# gator-bit.net
KiCad netlist of a schematic drawn in EAGLE
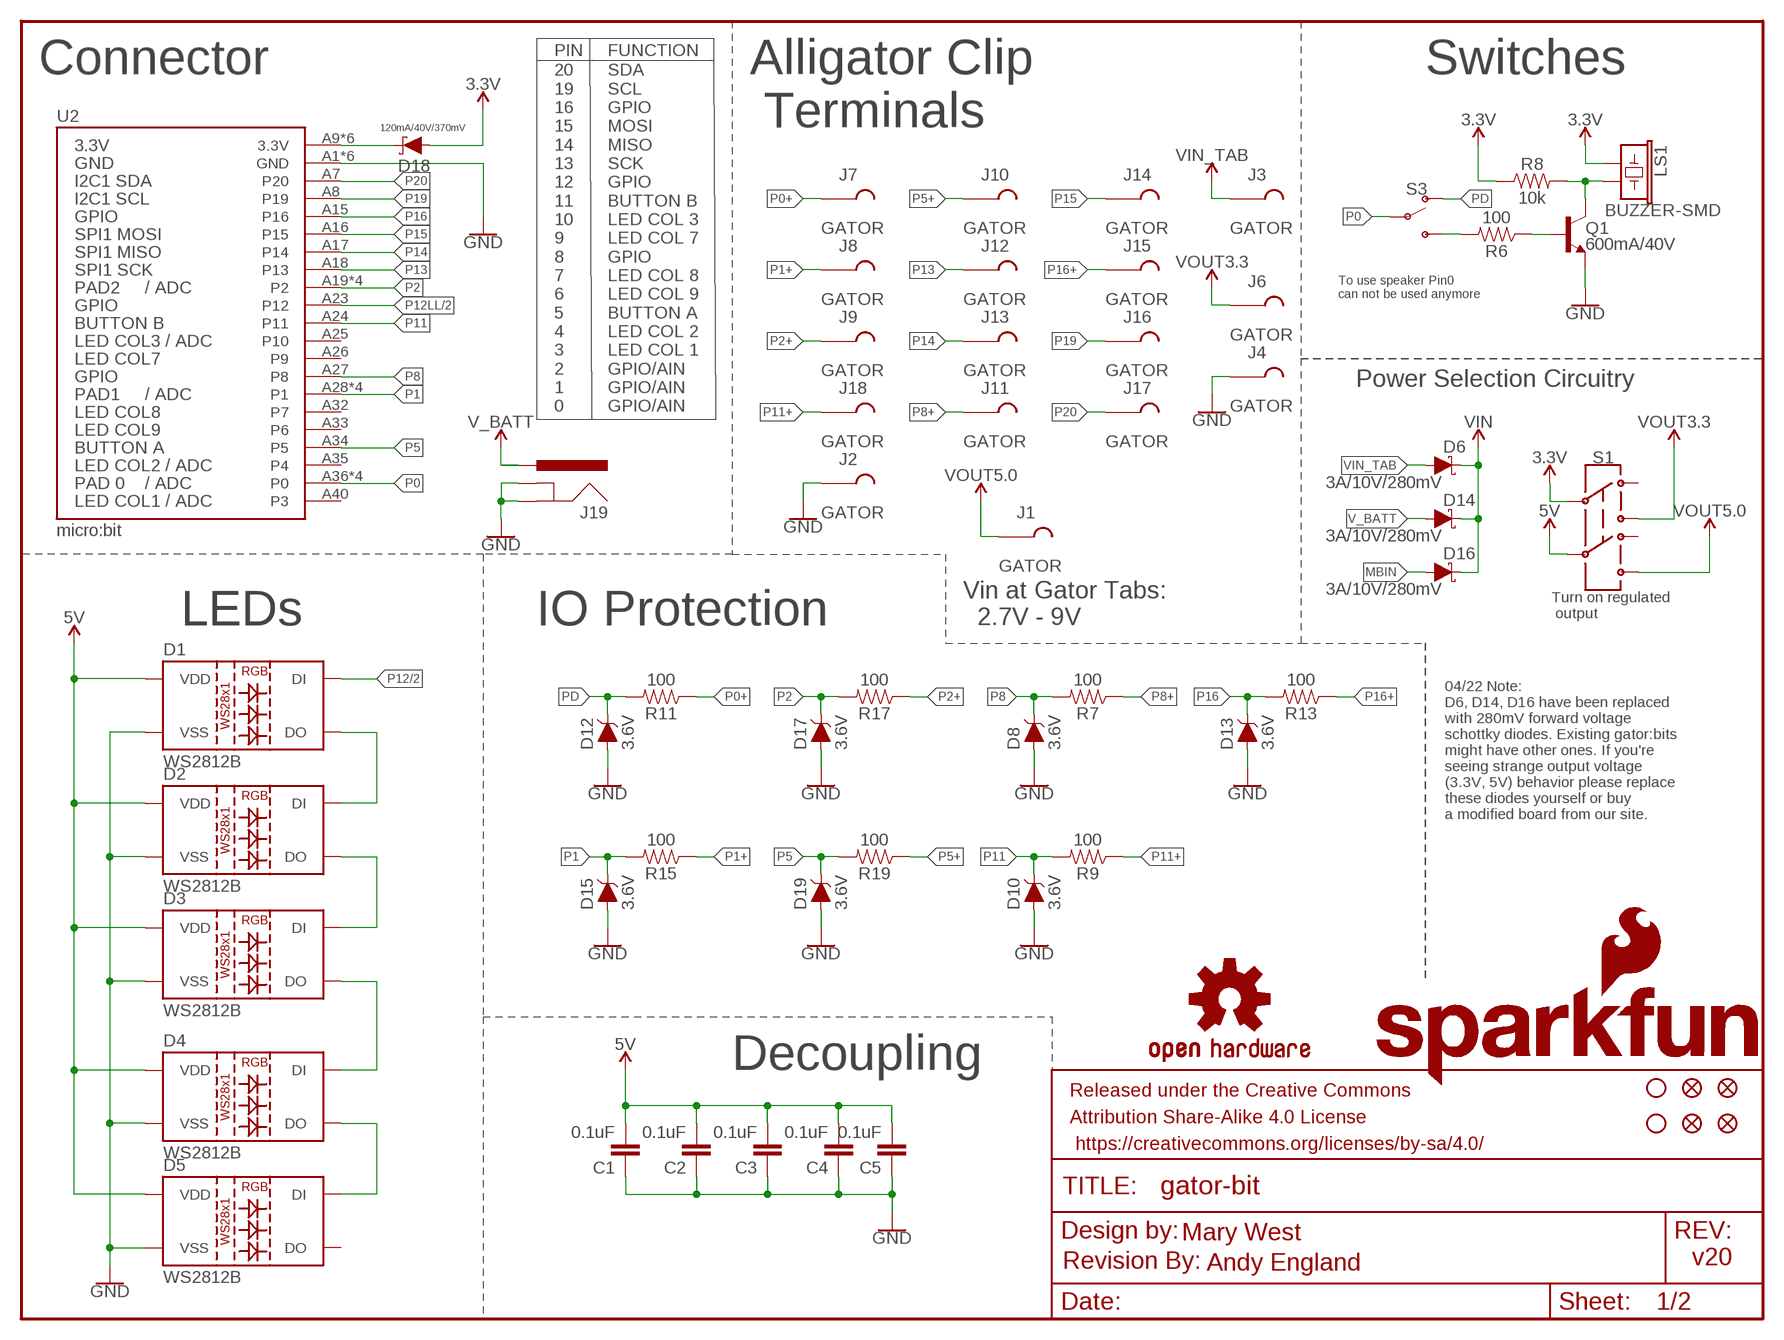
[diagram p0: schematic, sheet 1]
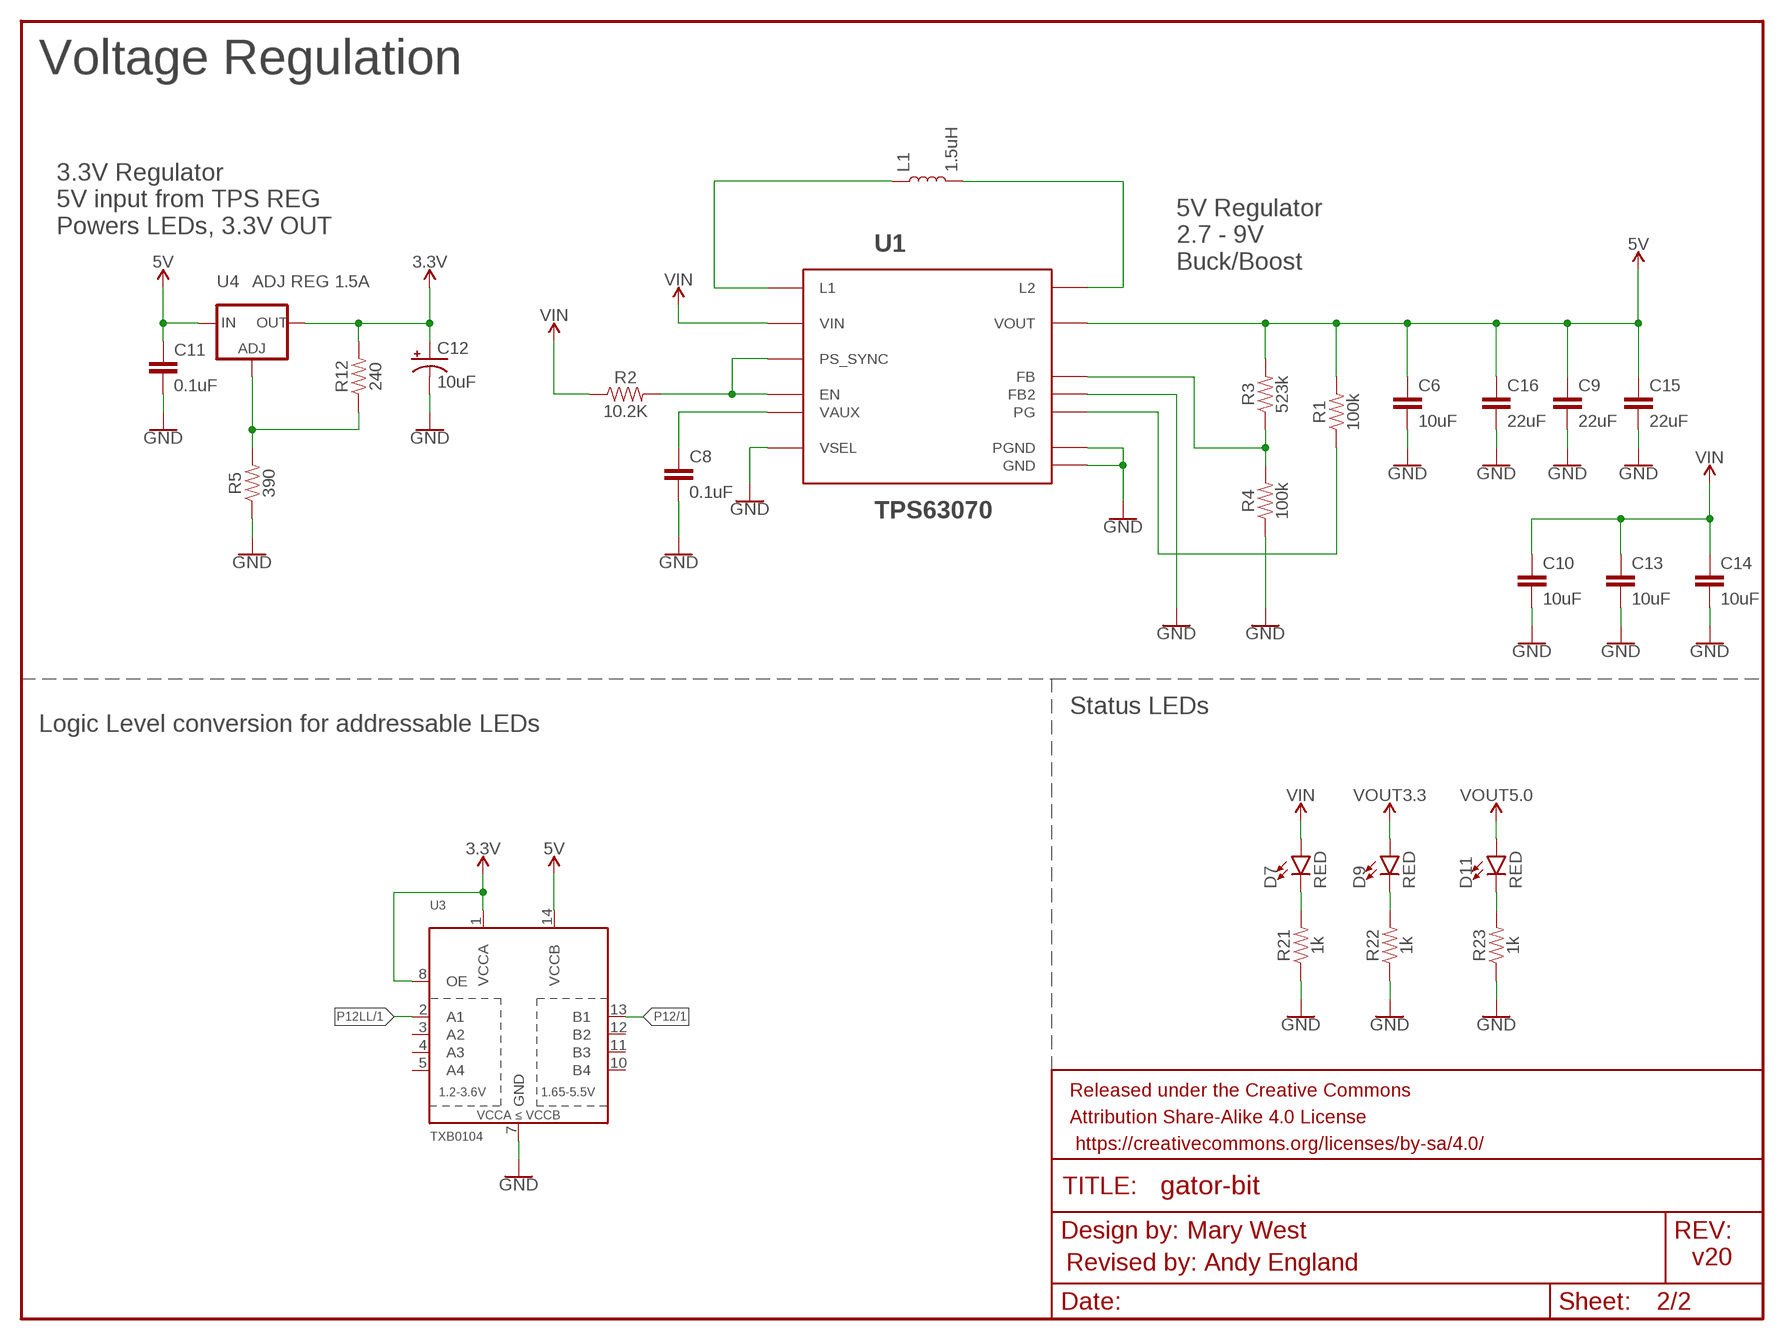
[diagram p1: schematic, sheet 2]

(export (version "E")
  (design (tool "Eeschema 10.0.6"))
  (components
    (comp (ref "C6")
      (value "10uF")
      (footprint "eagle-import:0603")
      (libsource (lib "eagle-import") (part "10UF-0603-6.3V-20%"))
    )
    (comp (ref "C8")
      (value "0.1uF")
      (footprint "eagle-import:0603")
      (libsource (lib "eagle-import") (part "0.1UF-0603-25V-(+80/-20%)"))
    )
    (comp (ref "C9")
      (value "22uF")
      (footprint "eagle-import:0805")
      (libsource (lib "eagle-import") (part "22UF-0805-6.3V-20%"))
    )
    (comp (ref "C10")
      (value "10uF")
      (footprint "eagle-import:0805")
      (libsource (lib "eagle-import") (part "10UF-0805-10V-10%"))
    )
    (comp (ref "C11")
      (value "0.1uF")
      (footprint "eagle-import:0603")
      (libsource (lib "eagle-import") (part "0.1UF-0603-25V-(+80/-20%)"))
    )
    (comp (ref "C12")
      (value "10uF")
      (footprint "eagle-import:EIA3216")
      (libsource (lib "eagle-import") (part "10UF-POLAR-EIA3216-16V-10%(TANT)"))
    )
    (comp (ref "C13")
      (value "10uF")
      (footprint "eagle-import:0805")
      (libsource (lib "eagle-import") (part "10UF-0805-10V-10%"))
    )
    (comp (ref "C14")
      (value "10uF")
      (footprint "eagle-import:0603")
      (libsource (lib "eagle-import") (part "10UF-0603-6.3V-20%"))
    )
    (comp (ref "C15")
      (value "22uF")
      (footprint "eagle-import:0805")
      (libsource (lib "eagle-import") (part "22UF-0805-6.3V-20%"))
    )
    (comp (ref "C16")
      (value "22uF")
      (footprint "eagle-import:0805")
      (libsource (lib "eagle-import") (part "22UF-0805-6.3V-20%"))
    )
    (comp (ref "D7")
      (value "RED")
      (footprint "eagle-import:LED-0603")
      (libsource (lib "eagle-import") (part "LED-RED0603"))
    )
    (comp (ref "D9")
      (value "RED")
      (footprint "eagle-import:LED-0603")
      (libsource (lib "eagle-import") (part "LED-RED0603"))
    )
    (comp (ref "D11")
      (value "RED")
      (footprint "eagle-import:LED-0603")
      (libsource (lib "eagle-import") (part "LED-RED0603"))
    )
    (comp (ref "FRAME3")
      (value "FRAME-LETTER")
      (footprint "eagle-import:CREATIVE_COMMONS")
      (libsource (lib "eagle-import") (part "FRAME-LETTER"))
    )
    (comp (ref "L1")
      (value "1.5uH")
      (footprint "eagle-import:XFL4020")
      (libsource (lib "eagle-import") (part "INDUCTOR-XFL40201.5UH"))
    )
    (comp (ref "R1")
      (value "100k")
      (footprint "eagle-import:0603")
      (libsource (lib "eagle-import") (part "100KOHM-0603-1/10W-1%"))
    )
    (comp (ref "R2")
      (value "10.2K")
      (footprint "eagle-import:0603")
      (libsource (lib "eagle-import") (part "10.2KOHM"))
    )
    (comp (ref "R3")
      (value "523k")
      (footprint "eagle-import:0603")
      (libsource (lib "eagle-import") (part "523KOHMOHMS-0603-1/10W-1%"))
    )
    (comp (ref "R4")
      (value "100k")
      (footprint "eagle-import:0603")
      (libsource (lib "eagle-import") (part "100KOHM-0603-1/10W-1%"))
    )
    (comp (ref "R5")
      (value "390")
      (footprint "eagle-import:0603")
      (libsource (lib "eagle-import") (part "390OHM-0603-1/10W-1%"))
    )
    (comp (ref "R12")
      (value "240")
      (footprint "eagle-import:0603")
      (libsource (lib "eagle-import") (part "240OHM-0603-1/10W-1%"))
    )
    (comp (ref "R21")
      (value "1k")
      (footprint "eagle-import:0603")
      (libsource (lib "eagle-import") (part "1KOHM-0603-1/10W-1%"))
    )
    (comp (ref "R22")
      (value "1k")
      (footprint "eagle-import:0603")
      (libsource (lib "eagle-import") (part "1KOHM-0603-1/10W-1%"))
    )
    (comp (ref "R23")
      (value "1k")
      (footprint "eagle-import:0603")
      (libsource (lib "eagle-import") (part "1KOHM-0603-1/10W-1%"))
    )
    (comp (ref "U1")
      (value "TPS63070")
      (footprint "eagle-import:TPS63070RNM")
      (libsource (lib "eagle-import") (part "TPS63070RNM"))
    )
    (comp (ref "U3")
      (value "TXB0104")
      (footprint "eagle-import:TSSOP14")
      (libsource (lib "eagle-import") (part "TXB0104PWR"))
    )
    (comp (ref "U4")
      (value "ADJ REG 1.5A")
      (footprint "eagle-import:SOT223")
      (libsource (lib "eagle-import") (part "GATORBIT_LM317"))
    )
    (comp (ref "C1")
      (value "0.1uF")
      (footprint "eagle-import:0603")
      (libsource (lib "eagle-import") (part "0.1UF-0603-25V-(+80/-20%)"))
    )
    (comp (ref "C2")
      (value "0.1uF")
      (footprint "eagle-import:0603")
      (libsource (lib "eagle-import") (part "0.1UF-0603-25V-(+80/-20%)"))
    )
    (comp (ref "C3")
      (value "0.1uF")
      (footprint "eagle-import:0603")
      (libsource (lib "eagle-import") (part "0.1UF-0603-25V-(+80/-20%)"))
    )
    (comp (ref "C4")
      (value "0.1uF")
      (footprint "eagle-import:0603")
      (libsource (lib "eagle-import") (part "0.1UF-0603-25V-(+80/-20%)"))
    )
    (comp (ref "C5")
      (value "0.1uF")
      (footprint "eagle-import:0603")
      (libsource (lib "eagle-import") (part "0.1UF-0603-25V-(+80/-20%)"))
    )
    (comp (ref "D1")
      (value "WS2812B")
      (footprint "eagle-import:WS2812B")
      (libsource (lib "eagle-import") (part "WS2812B"))
    )
    (comp (ref "D2")
      (value "WS2812B")
      (footprint "eagle-import:WS2812B")
      (libsource (lib "eagle-import") (part "WS2812B"))
    )
    (comp (ref "D3")
      (value "WS2812B")
      (footprint "eagle-import:WS2812B")
      (libsource (lib "eagle-import") (part "WS2812B"))
    )
    (comp (ref "D4")
      (value "WS2812B")
      (footprint "eagle-import:WS2812B")
      (libsource (lib "eagle-import") (part "WS2812B"))
    )
    (comp (ref "D5")
      (value "WS2812B")
      (footprint "eagle-import:WS2812B")
      (libsource (lib "eagle-import") (part "WS2812B"))
    )
    (comp (ref "D6")
      (value "3A/10V/280mV")
      (footprint "eagle-import:SOD-323")
      (libsource (lib "eagle-import") (part "DIODE-SCHOTTKY-BAT60A"))
    )
    (comp (ref "D8")
      (value "3.6V")
      (footprint "eagle-import:SOD-323")
      (libsource (lib "eagle-import") (part "DIODE-ZENER-BZT52C3V6S"))
    )
    (comp (ref "D10")
      (value "3.6V")
      (footprint "eagle-import:SOD-323")
      (libsource (lib "eagle-import") (part "DIODE-ZENER-BZT52C3V6S"))
    )
    (comp (ref "D12")
      (value "3.6V")
      (footprint "eagle-import:SOD-323")
      (libsource (lib "eagle-import") (part "DIODE-ZENER-BZT52C3V6S"))
    )
    (comp (ref "D13")
      (value "3.6V")
      (footprint "eagle-import:SOD-323")
      (libsource (lib "eagle-import") (part "DIODE-ZENER-BZT52C3V6S"))
    )
    (comp (ref "D14")
      (value "3A/10V/280mV")
      (footprint "eagle-import:SOD-323")
      (libsource (lib "eagle-import") (part "DIODE-SCHOTTKY-BAT60A"))
    )
    (comp (ref "D15")
      (value "3.6V")
      (footprint "eagle-import:SOD-323")
      (libsource (lib "eagle-import") (part "DIODE-ZENER-BZT52C3V6S"))
    )
    (comp (ref "D16")
      (value "3A/10V/280mV")
      (footprint "eagle-import:SOD-323")
      (libsource (lib "eagle-import") (part "DIODE-SCHOTTKY-BAT60A"))
    )
    (comp (ref "D17")
      (value "3.6V")
      (footprint "eagle-import:SOD-323")
      (libsource (lib "eagle-import") (part "DIODE-ZENER-BZT52C3V6S"))
    )
    (comp (ref "D18")
      (value "120mA/40V/370mV")
      (footprint "eagle-import:SOD-523")
      (libsource (lib "eagle-import") (part "DIODE-SCHOTTKY-RB751S40"))
    )
    (comp (ref "D19")
      (value "3.6V")
      (footprint "eagle-import:SOD-323")
      (libsource (lib "eagle-import") (part "DIODE-ZENER-BZT52C3V6S"))
    )
    (comp (ref "FD1")
      (value "FIDUCIAL1X2")
      (footprint "eagle-import:FIDUCIAL-1X2")
      (libsource (lib "eagle-import") (part "FIDUCIAL1X2"))
    )
    (comp (ref "FD2")
      (value "FIDUCIAL1X2")
      (footprint "eagle-import:FIDUCIAL-1X2")
      (libsource (lib "eagle-import") (part "FIDUCIAL1X2"))
    )
    (comp (ref "FD3")
      (value "FIDUCIAL1X2")
      (footprint "eagle-import:FIDUCIAL-1X2")
      (libsource (lib "eagle-import") (part "FIDUCIAL1X2"))
    )
    (comp (ref "FD4")
      (value "FIDUCIAL1X2")
      (footprint "eagle-import:FIDUCIAL-1X2")
      (libsource (lib "eagle-import") (part "FIDUCIAL1X2"))
    )
    (comp (ref "FRAME1")
      (value "FRAME-LETTER")
      (footprint "eagle-import:CREATIVE_COMMONS")
      (libsource (lib "eagle-import") (part "FRAME-LETTER"))
    )
    (comp (ref "H1")
      (value "STAND-OFF")
      (footprint "eagle-import:STAND-OFF")
      (libsource (lib "eagle-import") (part "STAND-OFF"))
    )
    (comp (ref "H2")
      (value "STAND-OFF")
      (footprint "eagle-import:STAND-OFF")
      (libsource (lib "eagle-import") (part "STAND-OFF"))
    )
    (comp (ref "J1")
      (value "GATOR")
      (footprint "eagle-import:GATOR")
      (libsource (lib "eagle-import") (part "GATOR"))
    )
    (comp (ref "J2")
      (value "GATOR")
      (footprint "eagle-import:GATOR")
      (libsource (lib "eagle-import") (part "GATOR"))
    )
    (comp (ref "J3")
      (value "GATOR")
      (footprint "eagle-import:GATOR")
      (libsource (lib "eagle-import") (part "GATOR"))
    )
    (comp (ref "J4")
      (value "GATOR")
      (footprint "eagle-import:GATOR")
      (libsource (lib "eagle-import") (part "GATOR"))
    )
    (comp (ref "J6")
      (value "GATOR")
      (footprint "eagle-import:GATOR")
      (libsource (lib "eagle-import") (part "GATOR"))
    )
    (comp (ref "J7")
      (value "GATOR")
      (footprint "eagle-import:GATOR")
      (libsource (lib "eagle-import") (part "GATOR"))
    )
    (comp (ref "J8")
      (value "GATOR")
      (footprint "eagle-import:GATOR")
      (libsource (lib "eagle-import") (part "GATOR"))
    )
    (comp (ref "J9")
      (value "GATOR")
      (footprint "eagle-import:GATOR")
      (libsource (lib "eagle-import") (part "GATOR"))
    )
    (comp (ref "J10")
      (value "GATOR")
      (footprint "eagle-import:GATOR")
      (libsource (lib "eagle-import") (part "GATOR"))
    )
    (comp (ref "J11")
      (value "GATOR")
      (footprint "eagle-import:GATOR")
      (libsource (lib "eagle-import") (part "GATOR"))
    )
    (comp (ref "J12")
      (value "GATOR")
      (footprint "eagle-import:GATOR")
      (libsource (lib "eagle-import") (part "GATOR"))
    )
    (comp (ref "J13")
      (value "GATOR")
      (footprint "eagle-import:GATOR")
      (libsource (lib "eagle-import") (part "GATOR"))
    )
    (comp (ref "J14")
      (value "GATOR")
      (footprint "eagle-import:GATOR")
      (libsource (lib "eagle-import") (part "GATOR"))
    )
    (comp (ref "J15")
      (value "GATOR")
      (footprint "eagle-import:GATOR")
      (libsource (lib "eagle-import") (part "GATOR"))
    )
    (comp (ref "J16")
      (value "GATOR")
      (footprint "eagle-import:GATOR")
      (libsource (lib "eagle-import") (part "GATOR"))
    )
    (comp (ref "J17")
      (value "GATOR")
      (footprint "eagle-import:GATOR")
      (libsource (lib "eagle-import") (part "GATOR"))
    )
    (comp (ref "J18")
      (value "GATOR")
      (footprint "eagle-import:GATOR")
      (libsource (lib "eagle-import") (part "GATOR"))
    )
    (comp (ref "J19")
      (value "POWER_JACKPTH_LOCK")
      (footprint "eagle-import:POWER_JACK_PTH_LOCK")
      (libsource (lib "eagle-import") (part "POWER_JACKPTH_LOCK"))
    )
    (comp (ref "LOGO1")
      (value "SFE_LOGO_NAME_FLAME.3_INCH")
      (footprint "eagle-import:SFE_LOGO_NAME_FLAME_.3")
      (libsource (lib "eagle-import") (part "SFE_LOGO_NAME_FLAME.3_INCH"))
    )
    (comp (ref "LOGO2")
      (value "OSHW-LOGOM")
      (footprint "eagle-import:OSHW-LOGO-M")
      (libsource (lib "eagle-import") (part "OSHW-LOGOM"))
    )
    (comp (ref "LOGO3")
      (value "REVISION")
      (footprint "eagle-import:REVISION")
      (libsource (lib "eagle-import") (part "REVISION"))
    )
    (comp (ref "LS1")
      (value "BUZZER-SMD")
      (footprint "eagle-import:BUZZER-CCV")
      (libsource (lib "eagle-import") (part "BUZZER-SMD"))
    )
    (comp (ref "Q1")
      (value "600mA/40V")
      (footprint "eagle-import:SOT23-3")
      (libsource (lib "eagle-import") (part "TRANS_NPN-MMBT2222AL"))
    )
    (comp (ref "R6")
      (value "100")
      (footprint "eagle-import:0603")
      (libsource (lib "eagle-import") (part "100OHM-0603-1/10W-1%"))
    )
    (comp (ref "R7")
      (value "100")
      (footprint "eagle-import:0603")
      (libsource (lib "eagle-import") (part "100OHM-0603-1/10W-1%"))
    )
    (comp (ref "R8")
      (value "10k")
      (footprint "eagle-import:0603")
      (libsource (lib "eagle-import") (part "10KOHM-0603-1/10W-1%"))
    )
    (comp (ref "R9")
      (value "100")
      (footprint "eagle-import:0603")
      (libsource (lib "eagle-import") (part "100OHM-0603-1/10W-1%"))
    )
    (comp (ref "R11")
      (value "100")
      (footprint "eagle-import:0603")
      (libsource (lib "eagle-import") (part "100OHM-0603-1/10W-1%"))
    )
    (comp (ref "R13")
      (value "100")
      (footprint "eagle-import:0603")
      (libsource (lib "eagle-import") (part "100OHM-0603-1/10W-1%"))
    )
    (comp (ref "R15")
      (value "100")
      (footprint "eagle-import:0603")
      (libsource (lib "eagle-import") (part "100OHM-0603-1/10W-1%"))
    )
    (comp (ref "R17")
      (value "100")
      (footprint "eagle-import:0603")
      (libsource (lib "eagle-import") (part "100OHM-0603-1/10W-1%"))
    )
    (comp (ref "R19")
      (value "100")
      (footprint "eagle-import:0603")
      (libsource (lib "eagle-import") (part "100OHM-0603-1/10W-1%"))
    )
    (comp (ref "S1")
      (value "SWITCH-DPDT-SMD-AYZ0202")
      (footprint "eagle-import:SWITCH_DPDT_SMD_AYZ0202")
      (libsource (lib "eagle-import") (part "SWITCH-DPDT-SMD-AYZ0202"))
    )
    (comp (ref "S3")
      (value "SWITCH-SPDT-SMD-AYZ0202")
      (footprint "eagle-import:SWITCH_DPDT_SMD_AYZ0202")
      (libsource (lib "eagle-import") (part "SWITCH-SPDT-SMD-AYZ0202"))
    )
    (comp (ref "U2")
      (value "micro:bit")
      (footprint "eagle-import:MICRO_BIT_RA_PTH")
      (libsource (lib "eagle-import") (part "MICRO{colon}BITLEDS_UP"))
    )
  )
  (nets
    (net (code "1") (name "3.3V") (class "Default")
      (node (ref "C12") (pin "+") (pinfunction "+_+") (pintype "passive"))
      (node (ref "D18") (pin "A") (pinfunction "A_A") (pintype "passive"))
      (node (ref "LS1") (pin "+") (pinfunction "1_+") (pintype "passive"))
      (node (ref "R12") (pin "2") (pinfunction "2_2") (pintype "passive"))
      (node (ref "R8") (pin "1") (pinfunction "1_1") (pintype "passive"))
      (node (ref "S1") (pin "2") (pinfunction "2_2") (pintype "bidirectional"))
      (node (ref "U3") (pin "1") (pinfunction "VCCA_1") (pintype "bidirectional"))
      (node (ref "U3") (pin "8") (pinfunction "OE_8") (pintype "bidirectional"))
      (node (ref "U4") (pin "2") (pinfunction "OUT_2") (pintype "output"))
      (node (ref "U4") (pin "4") (pinfunction "OUT_4") (pintype "output"))
    )
    (net (code "2") (name "5V") (class "Default")
      (node (ref "C1") (pin "2") (pinfunction "2_2") (pintype "passive"))
      (node (ref "C11") (pin "1") (pinfunction "1_1") (pintype "passive"))
      (node (ref "C15") (pin "1") (pinfunction "1_1") (pintype "passive"))
      (node (ref "C16") (pin "1") (pinfunction "1_1") (pintype "passive"))
      (node (ref "C2") (pin "2") (pinfunction "2_2") (pintype "passive"))
      (node (ref "C3") (pin "2") (pinfunction "2_2") (pintype "passive"))
      (node (ref "C4") (pin "2") (pinfunction "2_2") (pintype "passive"))
      (node (ref "C5") (pin "2") (pinfunction "2_2") (pintype "passive"))
      (node (ref "C6") (pin "1") (pinfunction "1_1") (pintype "passive"))
      (node (ref "C9") (pin "1") (pinfunction "1_1") (pintype "passive"))
      (node (ref "D1") (pin "1") (pinfunction "VDD_1") (pintype "bidirectional"))
      (node (ref "D2") (pin "1") (pinfunction "VDD_1") (pintype "bidirectional"))
      (node (ref "D3") (pin "1") (pinfunction "VDD_1") (pintype "bidirectional"))
      (node (ref "D4") (pin "1") (pinfunction "VDD_1") (pintype "bidirectional"))
      (node (ref "D5") (pin "1") (pinfunction "VDD_1") (pintype "bidirectional"))
      (node (ref "R1") (pin "2") (pinfunction "2_2") (pintype "passive"))
      (node (ref "R3") (pin "2") (pinfunction "2_2") (pintype "passive"))
      (node (ref "S1") (pin "5") (pinfunction "5_5") (pintype "bidirectional"))
      (node (ref "U1") (pin "P$7") (pinfunction "VOUT_P$7") (pintype "bidirectional"))
      (node (ref "U3") (pin "14") (pinfunction "VCCB_14") (pintype "bidirectional"))
      (node (ref "U4") (pin "3") (pinfunction "IN_3") (pintype "input"))
    )
    (net (code "3") (name "GND") (class "Default")
      (node (ref "C1") (pin "1") (pinfunction "1_1") (pintype "passive"))
      (node (ref "C10") (pin "2") (pinfunction "2_2") (pintype "passive"))
      (node (ref "C11") (pin "2") (pinfunction "2_2") (pintype "passive"))
      (node (ref "C12") (pin "-") (pinfunction "-_-") (pintype "passive"))
      (node (ref "C13") (pin "2") (pinfunction "2_2") (pintype "passive"))
      (node (ref "C14") (pin "2") (pinfunction "2_2") (pintype "passive"))
      (node (ref "C15") (pin "2") (pinfunction "2_2") (pintype "passive"))
      (node (ref "C16") (pin "2") (pinfunction "2_2") (pintype "passive"))
      (node (ref "C2") (pin "1") (pinfunction "1_1") (pintype "passive"))
      (node (ref "C3") (pin "1") (pinfunction "1_1") (pintype "passive"))
      (node (ref "C4") (pin "1") (pinfunction "1_1") (pintype "passive"))
      (node (ref "C5") (pin "1") (pinfunction "1_1") (pintype "passive"))
      (node (ref "C6") (pin "2") (pinfunction "2_2") (pintype "passive"))
      (node (ref "C8") (pin "2") (pinfunction "2_2") (pintype "passive"))
      (node (ref "C9") (pin "2") (pinfunction "2_2") (pintype "passive"))
      (node (ref "D1") (pin "3") (pinfunction "VSS_3") (pintype "bidirectional"))
      (node (ref "D10") (pin "A") (pinfunction "A_A") (pintype "passive"))
      (node (ref "D12") (pin "A") (pinfunction "A_A") (pintype "passive"))
      (node (ref "D13") (pin "A") (pinfunction "A_A") (pintype "passive"))
      (node (ref "D15") (pin "A") (pinfunction "A_A") (pintype "passive"))
      (node (ref "D17") (pin "A") (pinfunction "A_A") (pintype "passive"))
      (node (ref "D19") (pin "A") (pinfunction "A_A") (pintype "passive"))
      (node (ref "D2") (pin "3") (pinfunction "VSS_3") (pintype "bidirectional"))
      (node (ref "D3") (pin "3") (pinfunction "VSS_3") (pintype "bidirectional"))
      (node (ref "D4") (pin "3") (pinfunction "VSS_3") (pintype "bidirectional"))
      (node (ref "D5") (pin "3") (pinfunction "VSS_3") (pintype "bidirectional"))
      (node (ref "D8") (pin "A") (pinfunction "A_A") (pintype "passive"))
      (node (ref "J19") (pin "GND") (pinfunction "GND_GND") (pintype "bidirectional"))
      (node (ref "J19") (pin "GNDBREAK") (pinfunction "GNDBREAK_GNDBREAK") (pintype "bidirectional"))
      (node (ref "J2") (pin "P$1") (pinfunction "P$1_P$1") (pintype "bidirectional"))
      (node (ref "J2") (pin "P$2") (pinfunction "P$1_P$2") (pintype "bidirectional"))
      (node (ref "J4") (pin "P$1") (pinfunction "P$1_P$1") (pintype "bidirectional"))
      (node (ref "J4") (pin "P$2") (pinfunction "P$1_P$2") (pintype "bidirectional"))
      (node (ref "Q1") (pin "2") (pinfunction "E_2") (pintype "passive"))
      (node (ref "R21") (pin "1") (pinfunction "1_1") (pintype "passive"))
      (node (ref "R22") (pin "1") (pinfunction "1_1") (pintype "passive"))
      (node (ref "R23") (pin "1") (pinfunction "1_1") (pintype "passive"))
      (node (ref "R4") (pin "1") (pinfunction "1_1") (pintype "passive"))
      (node (ref "R5") (pin "1") (pinfunction "1_1") (pintype "passive"))
      (node (ref "U1") (pin "P$10") (pinfunction "PGND_P$10") (pintype "bidirectional"))
      (node (ref "U1") (pin "P$15") (pinfunction "VSEL_P$15") (pintype "bidirectional"))
      (node (ref "U1") (pin "P$4") (pinfunction "GND_P$4") (pintype "bidirectional"))
      (node (ref "U1") (pin "P$6") (pinfunction "FB2_P$6") (pintype "bidirectional"))
      (node (ref "U2") (pin "A1") (pinfunction "GND_A1") (pintype "bidirectional"))
      (node (ref "U2") (pin "A2") (pinfunction "GND_A2") (pintype "bidirectional"))
      (node (ref "U2") (pin "A3") (pinfunction "GND_A3") (pintype "bidirectional"))
      (node (ref "U2") (pin "A4") (pinfunction "GND_A4") (pintype "bidirectional"))
      (node (ref "U2") (pin "A5") (pinfunction "GND_A5") (pintype "bidirectional"))
      (node (ref "U2") (pin "A6") (pinfunction "GND_A6") (pintype "bidirectional"))
      (node (ref "U3") (pin "7") (pinfunction "GND_7") (pintype "bidirectional"))
    )
    (net (code "4") (name "MBIN") (class "Default")
      (node (ref "D16") (pin "A") (pinfunction "A_A") (pintype "passive"))
      (node (ref "D18") (pin "C") (pinfunction "C_C") (pintype "passive"))
      (node (ref "U2") (pin "A10") (pinfunction "3.3V_A10") (pintype "bidirectional"))
      (node (ref "U2") (pin "A11") (pinfunction "3.3V_A11") (pintype "bidirectional"))
      (node (ref "U2") (pin "A12") (pinfunction "3.3V_A12") (pintype "bidirectional"))
      (node (ref "U2") (pin "A13") (pinfunction "3.3V_A13") (pintype "bidirectional"))
      (node (ref "U2") (pin "A14") (pinfunction "3.3V_A14") (pintype "bidirectional"))
      (node (ref "U2") (pin "A9") (pinfunction "3.3V_A9") (pintype "bidirectional"))
    )
    (net (code "5") (name "Net-(D1-DO)") (class "Default")
      (node (ref "D1") (pin "2") (pinfunction "DO_2") (pintype "bidirectional"))
      (node (ref "D2") (pin "4") (pinfunction "DI_4") (pintype "bidirectional"))
    )
    (net (code "6") (name "Net-(D2-DO)") (class "Default")
      (node (ref "D2") (pin "2") (pinfunction "DO_2") (pintype "bidirectional"))
      (node (ref "D3") (pin "4") (pinfunction "DI_4") (pintype "bidirectional"))
    )
    (net (code "7") (name "Net-(D3-DO)") (class "Default")
      (node (ref "D3") (pin "2") (pinfunction "DO_2") (pintype "bidirectional"))
      (node (ref "D4") (pin "4") (pinfunction "DI_4") (pintype "bidirectional"))
    )
    (net (code "8") (name "Net-(D4-DO)") (class "Default")
      (node (ref "D4") (pin "2") (pinfunction "DO_2") (pintype "bidirectional"))
      (node (ref "D5") (pin "4") (pinfunction "DI_4") (pintype "bidirectional"))
    )
    (net (code "9") (name "Net-(D7-PadC)") (class "Default")
      (node (ref "D7") (pin "C") (pinfunction "C_C") (pintype "passive"))
      (node (ref "R21") (pin "2") (pinfunction "2_2") (pintype "passive"))
    )
    (net (code "10") (name "Net-(D9-PadC)") (class "Default")
      (node (ref "D9") (pin "C") (pinfunction "C_C") (pintype "passive"))
      (node (ref "R22") (pin "2") (pinfunction "2_2") (pintype "passive"))
    )
    (net (code "11") (name "Net-(D11-PadC)") (class "Default")
      (node (ref "D11") (pin "C") (pinfunction "C_C") (pintype "passive"))
      (node (ref "R23") (pin "2") (pinfunction "2_2") (pintype "passive"))
    )
    (net (code "12") (name "Net-(L1-1)") (class "Default")
      (node (ref "L1") (pin "P$1") (pinfunction "1_P$1") (pintype "passive"))
      (node (ref "U1") (pin "P$11") (pinfunction "L1_P$11") (pintype "bidirectional"))
    )
    (net (code "13") (name "Net-(L1-2)") (class "Default")
      (node (ref "L1") (pin "P$2") (pinfunction "2_P$2") (pintype "passive"))
      (node (ref "U1") (pin "P$9") (pinfunction "L2_P$9") (pintype "bidirectional"))
    )
    (net (code "14") (name "Net-(LS1-2)") (class "Default")
      (node (ref "LS1") (pin "-") (pinfunction "2_-") (pintype "passive"))
      (node (ref "Q1") (pin "3") (pinfunction "C_3") (pintype "passive"))
      (node (ref "R8") (pin "2") (pinfunction "2_2") (pintype "passive"))
    )
    (net (code "15") (name "Net-(Q1-B)") (class "Default")
      (node (ref "Q1") (pin "1") (pinfunction "B_1") (pintype "passive"))
      (node (ref "R6") (pin "1") (pinfunction "1_1") (pintype "passive"))
    )
    (net (code "16") (name "Net-(S3-S)") (class "Default")
      (node (ref "R6") (pin "2") (pinfunction "2_2") (pintype "passive"))
      (node (ref "S3") (pin "3") (pinfunction "S_3") (pintype "passive"))
    )
    (net (code "17") (name "Net-(U1-EN)") (class "Default")
      (node (ref "R2") (pin "2") (pinfunction "2_2") (pintype "passive"))
      (node (ref "U1") (pin "P$1") (pinfunction "PS_SYNC_P$1") (pintype "bidirectional"))
      (node (ref "U1") (pin "P$14") (pinfunction "EN_P$14") (pintype "bidirectional"))
    )
    (net (code "18") (name "Net-(U1-FB)") (class "Default")
      (node (ref "R3") (pin "1") (pinfunction "1_1") (pintype "passive"))
      (node (ref "R4") (pin "2") (pinfunction "2_2") (pintype "passive"))
      (node (ref "U1") (pin "P$5") (pinfunction "FB_P$5") (pintype "bidirectional"))
    )
    (net (code "19") (name "Net-(U1-PG)") (class "Default")
      (node (ref "R1") (pin "1") (pinfunction "1_1") (pintype "passive"))
      (node (ref "U1") (pin "P$2") (pinfunction "PG_P$2") (pintype "bidirectional"))
    )
    (net (code "20") (name "Net-(U1-VAUX)") (class "Default")
      (node (ref "C8") (pin "1") (pinfunction "1_1") (pintype "passive"))
      (node (ref "U1") (pin "P$3") (pinfunction "VAUX_P$3") (pintype "bidirectional"))
    )
    (net (code "21") (name "Net-(U4-ADJ)") (class "Default")
      (node (ref "R12") (pin "1") (pinfunction "1_1") (pintype "passive"))
      (node (ref "R5") (pin "2") (pinfunction "2_2") (pintype "passive"))
      (node (ref "U4") (pin "1") (pinfunction "ADJ_1") (pintype "input"))
    )
    (net (code "22") (name "P0") (class "Default")
      (node (ref "S3") (pin "2") (pinfunction "P_2") (pintype "passive"))
      (node (ref "U2") (pin "A36") (pinfunction "P0_A36") (pintype "bidirectional"))
      (node (ref "U2") (pin "A37") (pinfunction "P0_A37") (pintype "bidirectional"))
      (node (ref "U2") (pin "A38") (pinfunction "P0_A38") (pintype "bidirectional"))
      (node (ref "U2") (pin "A39") (pinfunction "P0_A39") (pintype "bidirectional"))
    )
    (net (code "23") (name "P0+") (class "Default")
      (node (ref "J7") (pin "P$1") (pinfunction "P$1_P$1") (pintype "bidirectional"))
      (node (ref "J7") (pin "P$2") (pinfunction "P$1_P$2") (pintype "bidirectional"))
      (node (ref "R11") (pin "1") (pinfunction "1_1") (pintype "passive"))
    )
    (net (code "24") (name "P1") (class "Default")
      (node (ref "D15") (pin "C") (pinfunction "C_C") (pintype "passive"))
      (node (ref "R15") (pin "2") (pinfunction "2_2") (pintype "passive"))
      (node (ref "U2") (pin "A28") (pinfunction "P1_A28") (pintype "bidirectional"))
      (node (ref "U2") (pin "A29") (pinfunction "P1_A29") (pintype "bidirectional"))
      (node (ref "U2") (pin "A30") (pinfunction "P1_A30") (pintype "bidirectional"))
      (node (ref "U2") (pin "A31") (pinfunction "P1_A31") (pintype "bidirectional"))
    )
    (net (code "25") (name "P1+") (class "Default")
      (node (ref "J8") (pin "P$1") (pinfunction "P$1_P$1") (pintype "bidirectional"))
      (node (ref "J8") (pin "P$2") (pinfunction "P$1_P$2") (pintype "bidirectional"))
      (node (ref "R15") (pin "1") (pinfunction "1_1") (pintype "passive"))
    )
    (net (code "26") (name "P2") (class "Default")
      (node (ref "D17") (pin "C") (pinfunction "C_C") (pintype "passive"))
      (node (ref "R17") (pin "2") (pinfunction "2_2") (pintype "passive"))
      (node (ref "U2") (pin "A19") (pinfunction "P2_A19") (pintype "bidirectional"))
      (node (ref "U2") (pin "A20") (pinfunction "P2_A20") (pintype "bidirectional"))
      (node (ref "U2") (pin "A21") (pinfunction "P2_A21") (pintype "bidirectional"))
      (node (ref "U2") (pin "A22") (pinfunction "P2_A22") (pintype "bidirectional"))
    )
    (net (code "27") (name "P2+") (class "Default")
      (node (ref "J9") (pin "P$1") (pinfunction "P$1_P$1") (pintype "bidirectional"))
      (node (ref "J9") (pin "P$2") (pinfunction "P$1_P$2") (pintype "bidirectional"))
      (node (ref "R17") (pin "1") (pinfunction "1_1") (pintype "passive"))
    )
    (net (code "28") (name "P5") (class "Default")
      (node (ref "D19") (pin "C") (pinfunction "C_C") (pintype "passive"))
      (node (ref "R19") (pin "2") (pinfunction "2_2") (pintype "passive"))
      (node (ref "U2") (pin "A34") (pinfunction "P5_A34") (pintype "bidirectional"))
    )
    (net (code "29") (name "P5+") (class "Default")
      (node (ref "J10") (pin "P$1") (pinfunction "P$1_P$1") (pintype "bidirectional"))
      (node (ref "J10") (pin "P$2") (pinfunction "P$1_P$2") (pintype "bidirectional"))
      (node (ref "R19") (pin "1") (pinfunction "1_1") (pintype "passive"))
    )
    (net (code "30") (name "P8") (class "Default")
      (node (ref "D8") (pin "C") (pinfunction "C_C") (pintype "passive"))
      (node (ref "R7") (pin "2") (pinfunction "2_2") (pintype "passive"))
      (node (ref "U2") (pin "A27") (pinfunction "P8_A27") (pintype "bidirectional"))
    )
    (net (code "31") (name "P8+") (class "Default")
      (node (ref "J11") (pin "P$1") (pinfunction "P$1_P$1") (pintype "bidirectional"))
      (node (ref "J11") (pin "P$2") (pinfunction "P$1_P$2") (pintype "bidirectional"))
      (node (ref "R7") (pin "1") (pinfunction "1_1") (pintype "passive"))
    )
    (net (code "32") (name "P11") (class "Default")
      (node (ref "D10") (pin "C") (pinfunction "C_C") (pintype "passive"))
      (node (ref "R9") (pin "2") (pinfunction "2_2") (pintype "passive"))
      (node (ref "U2") (pin "A24") (pinfunction "P11_A24") (pintype "bidirectional"))
    )
    (net (code "33") (name "P11+") (class "Default")
      (node (ref "J18") (pin "P$1") (pinfunction "P$1_P$1") (pintype "bidirectional"))
      (node (ref "J18") (pin "P$2") (pinfunction "P$1_P$2") (pintype "bidirectional"))
      (node (ref "R9") (pin "1") (pinfunction "1_1") (pintype "passive"))
    )
    (net (code "34") (name "P12") (class "Default")
      (node (ref "D1") (pin "4") (pinfunction "DI_4") (pintype "bidirectional"))
      (node (ref "U3") (pin "13") (pinfunction "B1_13") (pintype "bidirectional"))
    )
    (net (code "35") (name "P12LL") (class "Default")
      (node (ref "U2") (pin "A23") (pinfunction "P12_A23") (pintype "bidirectional"))
      (node (ref "U3") (pin "2") (pinfunction "A1_2") (pintype "bidirectional"))
    )
    (net (code "36") (name "P13") (class "Default")
      (node (ref "J12") (pin "P$1") (pinfunction "P$1_P$1") (pintype "bidirectional"))
      (node (ref "J12") (pin "P$2") (pinfunction "P$1_P$2") (pintype "bidirectional"))
      (node (ref "U2") (pin "A18") (pinfunction "P13_A18") (pintype "bidirectional"))
    )
    (net (code "37") (name "P14") (class "Default")
      (node (ref "J13") (pin "P$1") (pinfunction "P$1_P$1") (pintype "bidirectional"))
      (node (ref "J13") (pin "P$2") (pinfunction "P$1_P$2") (pintype "bidirectional"))
      (node (ref "U2") (pin "A17") (pinfunction "P14_A17") (pintype "bidirectional"))
    )
    (net (code "38") (name "P15") (class "Default")
      (node (ref "J14") (pin "P$1") (pinfunction "P$1_P$1") (pintype "bidirectional"))
      (node (ref "J14") (pin "P$2") (pinfunction "P$1_P$2") (pintype "bidirectional"))
      (node (ref "U2") (pin "A16") (pinfunction "P15_A16") (pintype "bidirectional"))
    )
    (net (code "39") (name "P16") (class "Default")
      (node (ref "D13") (pin "C") (pinfunction "C_C") (pintype "passive"))
      (node (ref "R13") (pin "2") (pinfunction "2_2") (pintype "passive"))
      (node (ref "U2") (pin "A15") (pinfunction "P16_A15") (pintype "bidirectional"))
    )
    (net (code "40") (name "P16+") (class "Default")
      (node (ref "J15") (pin "P$1") (pinfunction "P$1_P$1") (pintype "bidirectional"))
      (node (ref "J15") (pin "P$2") (pinfunction "P$1_P$2") (pintype "bidirectional"))
      (node (ref "R13") (pin "1") (pinfunction "1_1") (pintype "passive"))
    )
    (net (code "41") (name "P19") (class "Default")
      (node (ref "J16") (pin "P$1") (pinfunction "P$1_P$1") (pintype "bidirectional"))
      (node (ref "J16") (pin "P$2") (pinfunction "P$1_P$2") (pintype "bidirectional"))
      (node (ref "U2") (pin "A8") (pinfunction "P19_A8") (pintype "bidirectional"))
    )
    (net (code "42") (name "P20") (class "Default")
      (node (ref "J17") (pin "P$1") (pinfunction "P$1_P$1") (pintype "bidirectional"))
      (node (ref "J17") (pin "P$2") (pinfunction "P$1_P$2") (pintype "bidirectional"))
      (node (ref "U2") (pin "A7") (pinfunction "P20_A7") (pintype "bidirectional"))
    )
    (net (code "43") (name "PD") (class "Default")
      (node (ref "D12") (pin "C") (pinfunction "C_C") (pintype "passive"))
      (node (ref "R11") (pin "2") (pinfunction "2_2") (pintype "passive"))
      (node (ref "S3") (pin "1") (pinfunction "O_1") (pintype "passive"))
    )
    (net (code "44") (name "VIN") (class "Default")
      (node (ref "C10") (pin "1") (pinfunction "1_1") (pintype "passive"))
      (node (ref "C13") (pin "1") (pinfunction "1_1") (pintype "passive"))
      (node (ref "C14") (pin "1") (pinfunction "1_1") (pintype "passive"))
      (node (ref "D14") (pin "C") (pinfunction "C_C") (pintype "passive"))
      (node (ref "D16") (pin "C") (pinfunction "C_C") (pintype "passive"))
      (node (ref "D6") (pin "C") (pinfunction "C_C") (pintype "passive"))
      (node (ref "D7") (pin "A") (pinfunction "A_A") (pintype "passive"))
      (node (ref "R2") (pin "1") (pinfunction "1_1") (pintype "passive"))
      (node (ref "U1") (pin "P$12") (pinfunction "VIN_P$12") (pintype "bidirectional"))
    )
    (net (code "45") (name "VIN_TAB") (class "Default")
      (node (ref "D6") (pin "A") (pinfunction "A_A") (pintype "passive"))
      (node (ref "J3") (pin "P$1") (pinfunction "P$1_P$1") (pintype "bidirectional"))
      (node (ref "J3") (pin "P$2") (pinfunction "P$1_P$2") (pintype "bidirectional"))
    )
    (net (code "46") (name "VOUT3.3") (class "Default")
      (node (ref "D9") (pin "A") (pinfunction "A_A") (pintype "passive"))
      (node (ref "J6") (pin "P$1") (pinfunction "P$1_P$1") (pintype "bidirectional"))
      (node (ref "J6") (pin "P$2") (pinfunction "P$1_P$2") (pintype "bidirectional"))
      (node (ref "S1") (pin "3") (pinfunction "3_3") (pintype "bidirectional"))
    )
    (net (code "47") (name "VOUT5.0") (class "Default")
      (node (ref "D11") (pin "A") (pinfunction "A_A") (pintype "passive"))
      (node (ref "J1") (pin "P$1") (pinfunction "P$1_P$1") (pintype "bidirectional"))
      (node (ref "J1") (pin "P$2") (pinfunction "P$1_P$2") (pintype "bidirectional"))
      (node (ref "S1") (pin "6") (pinfunction "6_6") (pintype "bidirectional"))
    )
    (net (code "48") (name "V_BATT") (class "Default")
      (node (ref "D14") (pin "A") (pinfunction "A_A") (pintype "passive"))
      (node (ref "J19") (pin "PWR") (pinfunction "PWR_PWR") (pintype "bidirectional"))
    )
    (net (code "49") (name "unconnected-(D5-DO-Pad2)") (class "Default")
      (node (ref "D5") (pin "2") (pinfunction "DO_2") (pintype "bidirectional"))
    )
    (net (code "50") (name "unconnected-(S1-Pad1)") (class "Default")
      (node (ref "S1") (pin "1") (pinfunction "1_1") (pintype "bidirectional"))
    )
    (net (code "51") (name "unconnected-(S1-Pad4)") (class "Default")
      (node (ref "S1") (pin "4") (pinfunction "4_4") (pintype "bidirectional"))
    )
    (net (code "52") (name "unconnected-(U2-P3-PadA40)") (class "Default")
      (node (ref "U2") (pin "A40") (pinfunction "P3_A40") (pintype "bidirectional"))
    )
    (net (code "53") (name "unconnected-(U2-P4-PadA35)") (class "Default")
      (node (ref "U2") (pin "A35") (pinfunction "P4_A35") (pintype "bidirectional"))
    )
    (net (code "54") (name "unconnected-(U2-P6-PadA33)") (class "Default")
      (node (ref "U2") (pin "A33") (pinfunction "P6_A33") (pintype "bidirectional"))
    )
    (net (code "55") (name "unconnected-(U2-P7-PadA32)") (class "Default")
      (node (ref "U2") (pin "A32") (pinfunction "P7_A32") (pintype "bidirectional"))
    )
    (net (code "56") (name "unconnected-(U2-P9-PadA26)") (class "Default")
      (node (ref "U2") (pin "A26") (pinfunction "P9_A26") (pintype "bidirectional"))
    )
    (net (code "57") (name "unconnected-(U2-P10-PadA25)") (class "Default")
      (node (ref "U2") (pin "A25") (pinfunction "P10_A25") (pintype "bidirectional"))
    )
    (net (code "58") (name "unconnected-(U3-A2-Pad3)") (class "Default")
      (node (ref "U3") (pin "3") (pinfunction "A2_3") (pintype "bidirectional"))
    )
    (net (code "59") (name "unconnected-(U3-A3-Pad4)") (class "Default")
      (node (ref "U3") (pin "4") (pinfunction "A3_4") (pintype "bidirectional"))
    )
    (net (code "60") (name "unconnected-(U3-A4-Pad5)") (class "Default")
      (node (ref "U3") (pin "5") (pinfunction "A4_5") (pintype "bidirectional"))
    )
    (net (code "61") (name "unconnected-(U3-B2-Pad12)") (class "Default")
      (node (ref "U3") (pin "12") (pinfunction "B2_12") (pintype "bidirectional"))
    )
    (net (code "62") (name "unconnected-(U3-B3-Pad11)") (class "Default")
      (node (ref "U3") (pin "11") (pinfunction "B3_11") (pintype "bidirectional"))
    )
    (net (code "63") (name "unconnected-(U3-B4-Pad10)") (class "Default")
      (node (ref "U3") (pin "10") (pinfunction "B4_10") (pintype "bidirectional"))
    )
  )
)
